# 5-Memories.net
KiCad netlist of a schematic drawn in Altium Designer
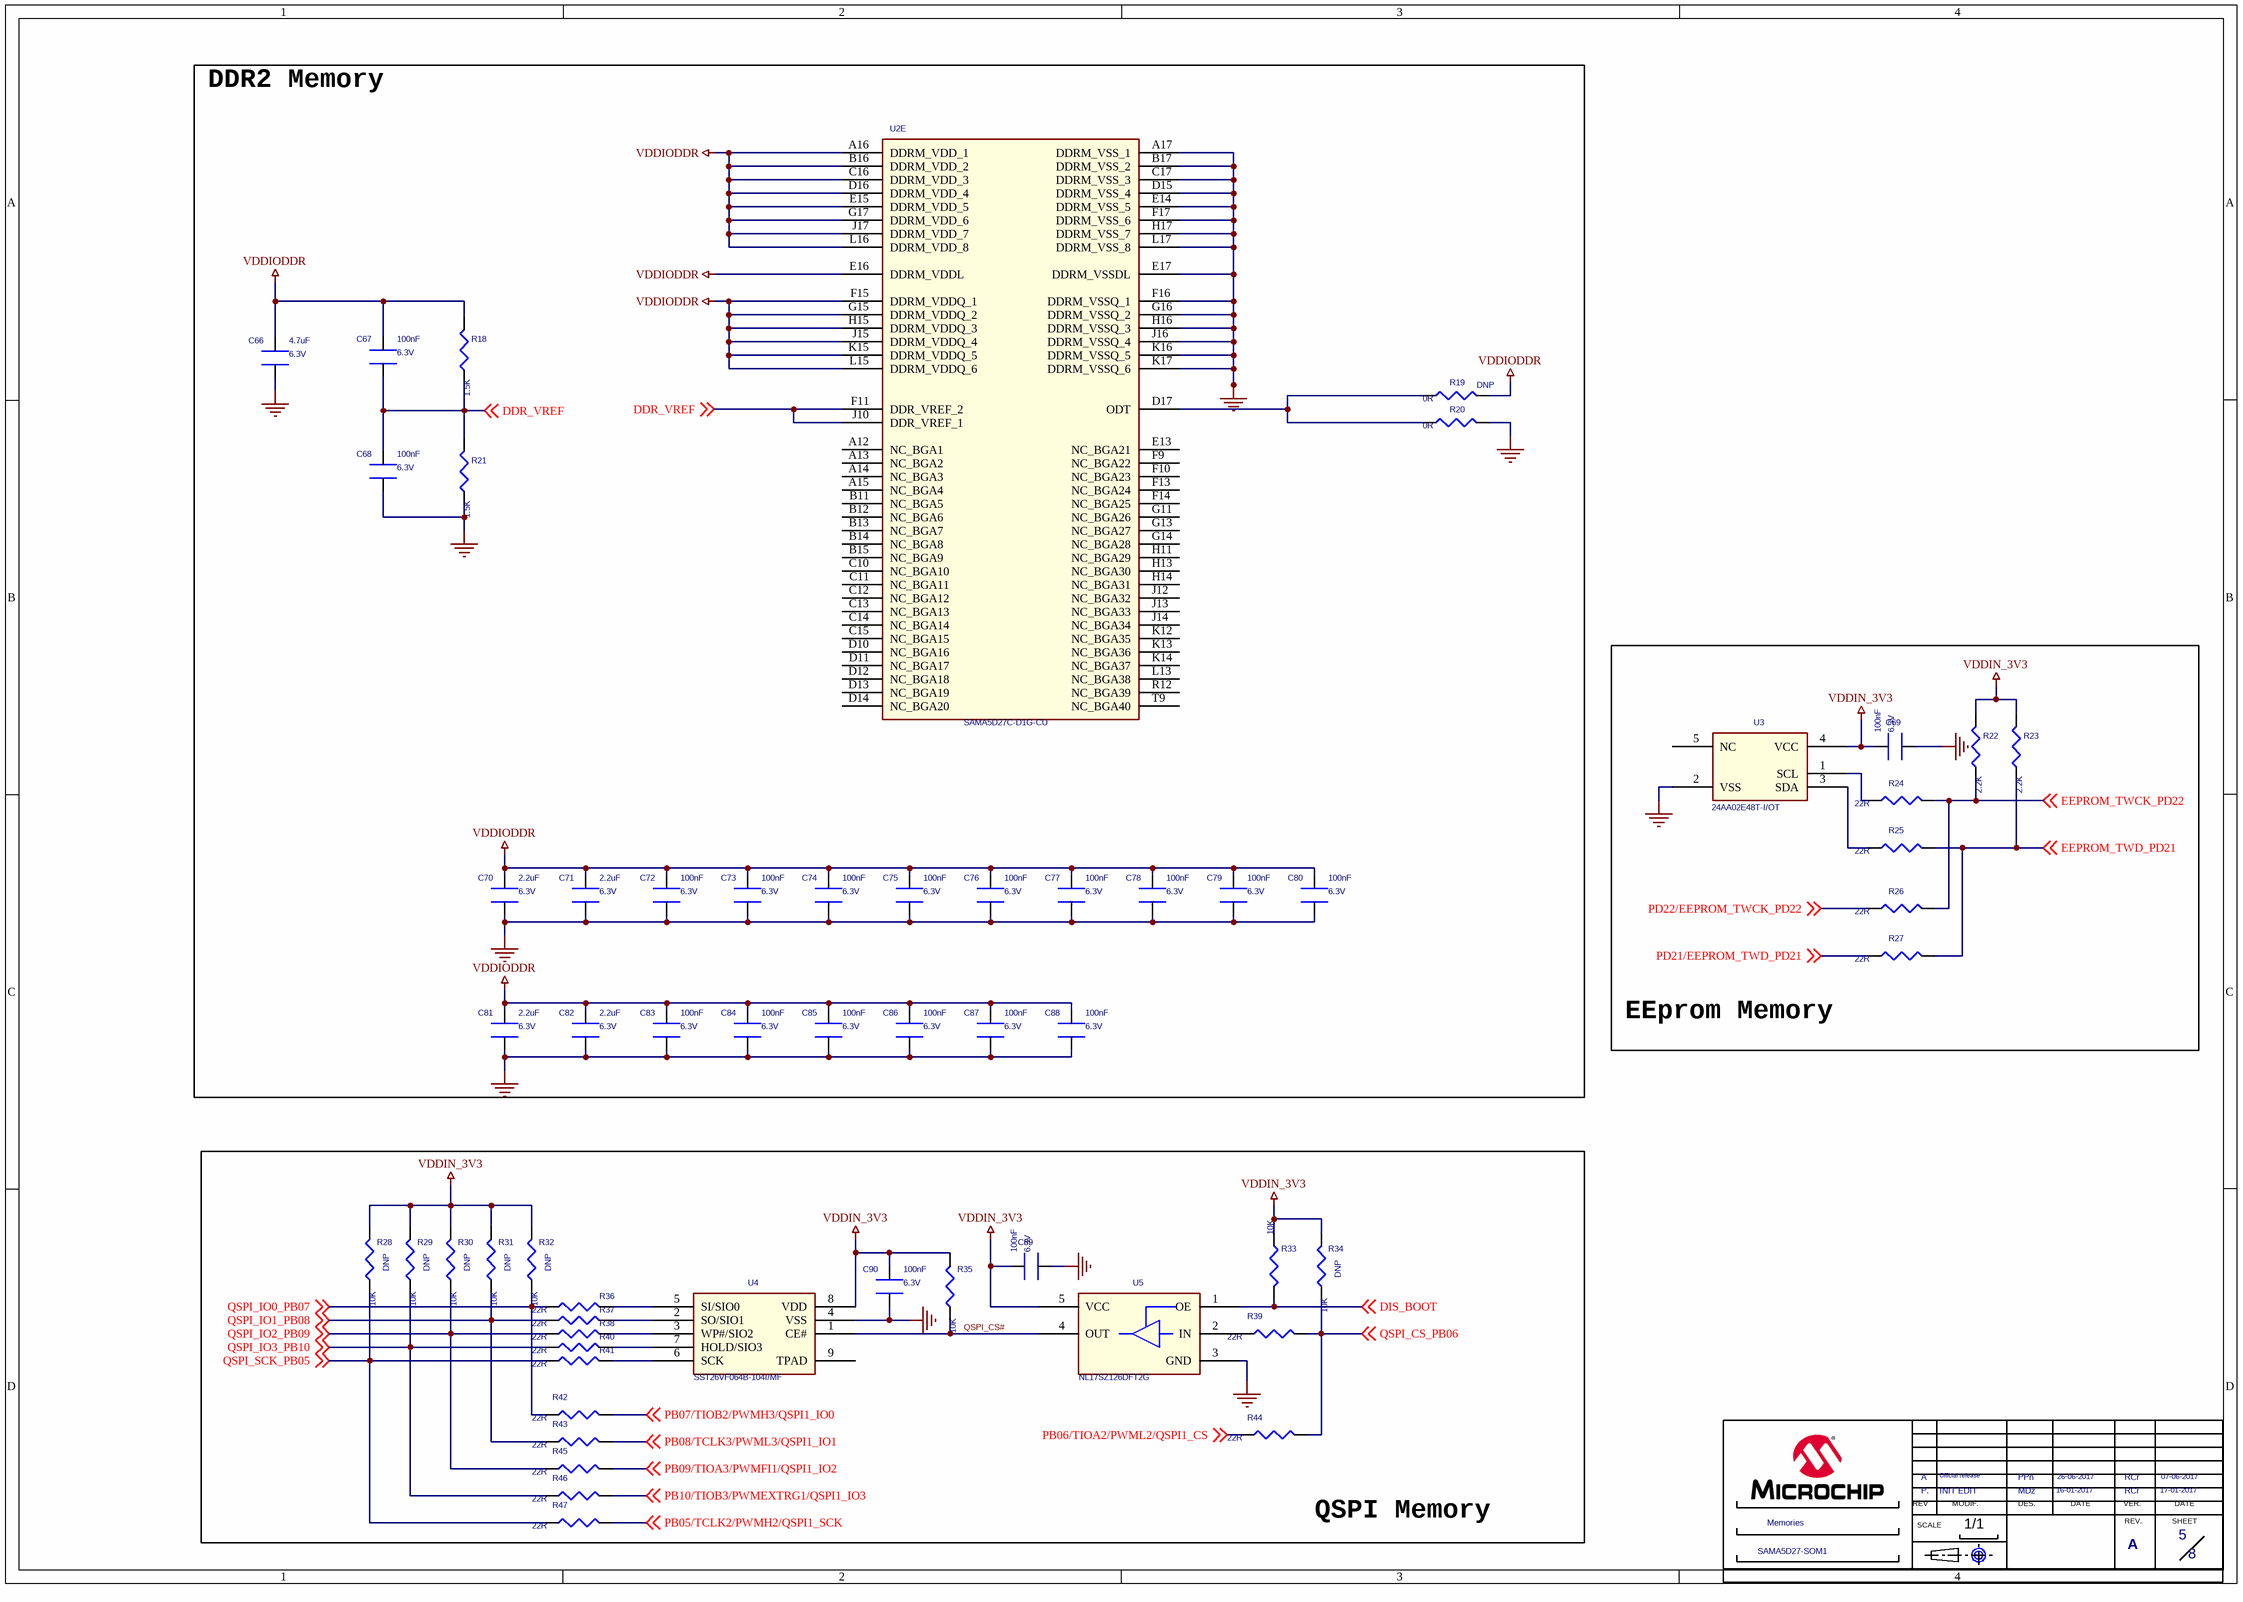
[diagram p0: 5-Memories.SchDoc]

(export (version "E")
  (design (tool "Eeschema 10.0.6"))
  (components
    (comp (ref "C66")
      (value "xpF x% xV")
      (footprint "C0402")
      (fields (field (name "TENSION") "6.3V") (field (name "VALEUR") "4.7uF") (field (name "HAUTEUR") "xmm"))
      (libsource (lib "*") (part "C0402-4.7uF-X5R-6.3V-10%"))
    )
    (comp (ref "C67")
      (value "xpF x% xV")
      (footprint "C0201")
      (fields (field (name "VALEUR") "100nF") (field (name "TENSION") "6.3V") (field (name "HAUTEUR") "xmm"))
      (libsource (lib "*") (part "C0201-100nF-X5R-6.3V"))
    )
    (comp (ref "C68")
      (value "xpF x% xV")
      (footprint "C0201")
      (fields (field (name "VALEUR") "100nF") (field (name "TENSION") "6.3V") (field (name "HAUTEUR") "xmm"))
      (libsource (lib "*") (part "C0201-100nF-X5R-6.3V"))
    )
    (comp (ref "C69")
      (value "xpF x% xV")
      (footprint "C0201")
      (fields (field (name "VALEUR") "100nF") (field (name "TENSION") "6.3V") (field (name "HAUTEUR") "xmm"))
      (libsource (lib "*") (part "C0201-100nF-X5R-6.3V"))
    )
    (comp (ref "C70")
      (value "xpF x% xV")
      (footprint "C0402")
      (fields (field (name "VALEUR") "2.2uF") (field (name "TENSION") "6.3V") (field (name "HAUTEUR") "xmm"))
      (libsource (lib "*") (part "C0402-2.2uF-X5R-6.3V"))
    )
    (comp (ref "C71")
      (value "xpF x% xV")
      (footprint "C0402")
      (fields (field (name "VALEUR") "2.2uF") (field (name "TENSION") "6.3V") (field (name "HAUTEUR") "xmm"))
      (libsource (lib "*") (part "C0402-2.2uF-X5R-6.3V"))
    )
    (comp (ref "C72")
      (value "xpF x% xV")
      (footprint "C0201")
      (fields (field (name "VALEUR") "100nF") (field (name "TENSION") "6.3V") (field (name "HAUTEUR") "xmm"))
      (libsource (lib "*") (part "C0201-100nF-X5R-6.3V"))
    )
    (comp (ref "C73")
      (value "xpF x% xV")
      (footprint "C0201")
      (fields (field (name "VALEUR") "100nF") (field (name "TENSION") "6.3V") (field (name "HAUTEUR") "xmm"))
      (libsource (lib "*") (part "C0201-100nF-X5R-6.3V"))
    )
    (comp (ref "C74")
      (value "xpF x% xV")
      (footprint "C0201")
      (fields (field (name "VALEUR") "100nF") (field (name "TENSION") "6.3V") (field (name "HAUTEUR") "xmm"))
      (libsource (lib "*") (part "C0201-100nF-X5R-6.3V"))
    )
    (comp (ref "C75")
      (value "xpF x% xV")
      (footprint "C0201")
      (fields (field (name "VALEUR") "100nF") (field (name "TENSION") "6.3V") (field (name "HAUTEUR") "xmm"))
      (libsource (lib "*") (part "C0201-100nF-X5R-6.3V"))
    )
    (comp (ref "C76")
      (value "xpF x% xV")
      (footprint "C0201")
      (fields (field (name "VALEUR") "100nF") (field (name "TENSION") "6.3V") (field (name "HAUTEUR") "xmm"))
      (libsource (lib "*") (part "C0201-100nF-X5R-6.3V"))
    )
    (comp (ref "C77")
      (value "xpF x% xV")
      (footprint "C0201")
      (fields (field (name "VALEUR") "100nF") (field (name "TENSION") "6.3V") (field (name "HAUTEUR") "xmm"))
      (libsource (lib "*") (part "C0201-100nF-X5R-6.3V"))
    )
    (comp (ref "C78")
      (value "xpF x% xV")
      (footprint "C0201")
      (fields (field (name "VALEUR") "100nF") (field (name "TENSION") "6.3V") (field (name "HAUTEUR") "xmm"))
      (libsource (lib "*") (part "C0201-100nF-X5R-6.3V"))
    )
    (comp (ref "C79")
      (value "xpF x% xV")
      (footprint "C0201")
      (fields (field (name "VALEUR") "100nF") (field (name "TENSION") "6.3V") (field (name "HAUTEUR") "xmm"))
      (libsource (lib "*") (part "C0201-100nF-X5R-6.3V"))
    )
    (comp (ref "C80")
      (value "xpF x% xV")
      (footprint "C0201")
      (fields (field (name "VALEUR") "100nF") (field (name "TENSION") "6.3V") (field (name "HAUTEUR") "xmm"))
      (libsource (lib "*") (part "C0201-100nF-X5R-6.3V"))
    )
    (comp (ref "C81")
      (value "xpF x% xV")
      (footprint "C0402")
      (fields (field (name "VALEUR") "2.2uF") (field (name "TENSION") "6.3V") (field (name "HAUTEUR") "xmm"))
      (libsource (lib "*") (part "C0402-2.2uF-X5R-6.3V"))
    )
    (comp (ref "C82")
      (value "xpF x% xV")
      (footprint "C0402")
      (fields (field (name "VALEUR") "2.2uF") (field (name "TENSION") "6.3V") (field (name "HAUTEUR") "xmm"))
      (libsource (lib "*") (part "C0402-2.2uF-X5R-6.3V"))
    )
    (comp (ref "C83")
      (value "xpF x% xV")
      (footprint "C0201")
      (fields (field (name "VALEUR") "100nF") (field (name "TENSION") "6.3V") (field (name "HAUTEUR") "xmm"))
      (libsource (lib "*") (part "C0201-100nF-X5R-6.3V"))
    )
    (comp (ref "C84")
      (value "xpF x% xV")
      (footprint "C0201")
      (fields (field (name "VALEUR") "100nF") (field (name "TENSION") "6.3V") (field (name "HAUTEUR") "xmm"))
      (libsource (lib "*") (part "C0201-100nF-X5R-6.3V"))
    )
    (comp (ref "C85")
      (value "xpF x% xV")
      (footprint "C0201")
      (fields (field (name "VALEUR") "100nF") (field (name "TENSION") "6.3V") (field (name "HAUTEUR") "xmm"))
      (libsource (lib "*") (part "C0201-100nF-X5R-6.3V"))
    )
    (comp (ref "C86")
      (value "xpF x% xV")
      (footprint "C0201")
      (fields (field (name "VALEUR") "100nF") (field (name "TENSION") "6.3V") (field (name "HAUTEUR") "xmm"))
      (libsource (lib "*") (part "C0201-100nF-X5R-6.3V"))
    )
    (comp (ref "C87")
      (value "xpF x% xV")
      (footprint "C0201")
      (fields (field (name "VALEUR") "100nF") (field (name "TENSION") "6.3V") (field (name "HAUTEUR") "xmm"))
      (libsource (lib "*") (part "C0201-100nF-X5R-6.3V"))
    )
    (comp (ref "C88")
      (value "xpF x% xV")
      (footprint "C0201")
      (fields (field (name "VALEUR") "100nF") (field (name "TENSION") "6.3V") (field (name "HAUTEUR") "xmm"))
      (libsource (lib "*") (part "C0201-100nF-X5R-6.3V"))
    )
    (comp (ref "C89")
      (value "xpF x% xV")
      (footprint "C0201")
      (fields (field (name "VALEUR") "100nF") (field (name "TENSION") "6.3V") (field (name "HAUTEUR") "xmm"))
      (libsource (lib "*") (part "C0201-100nF-X5R-6.3V"))
    )
    (comp (ref "C90")
      (value "xpF x% xV")
      (footprint "C0201")
      (fields (field (name "VALEUR") "100nF") (field (name "TENSION") "6.3V") (field (name "HAUTEUR") "xmm"))
      (libsource (lib "*") (part "C0201-100nF-X5R-6.3V"))
    )
    (comp (ref "R18")
      (value "xR x% xW")
      (footprint "R0201")
      (fields (field (name "VALEUR") "1.5K") (field (name "TOLERANCE") "1%"))
      (libsource (lib "*") (part "R0201-1.5K-1%"))
    )
    (comp (ref "R19")
      (value "xR x% xW")
      (footprint "R0201")
      (fields (field (name "VALEUR") "0R") (field (name "TOLERANCE") "x%") (field (name "DNP") "DNP"))
      (libsource (lib "*") (part "R0201-0R"))
    )
    (comp (ref "R20")
      (value "xR x% xW")
      (footprint "R0201")
      (fields (field (name "VALEUR") "0R") (field (name "TOLERANCE") "x%"))
      (libsource (lib "*") (part "R0201-0R"))
    )
    (comp (ref "R21")
      (value "xR x% xW")
      (footprint "R0201")
      (fields (field (name "VALEUR") "1.5K") (field (name "TOLERANCE") "1%"))
      (libsource (lib "*") (part "R0201-1.5K-1%"))
    )
    (comp (ref "R22")
      (value "xR x% xW")
      (footprint "R0201")
      (fields (field (name "TOLERANCE") "5%") (field (name "VALEUR") "2.2K"))
      (libsource (lib "*") (part "R0201-2.2K-5%"))
    )
    (comp (ref "R23")
      (value "xR x% xW")
      (footprint "R0201")
      (fields (field (name "TOLERANCE") "5%") (field (name "VALEUR") "2.2K"))
      (libsource (lib "*") (part "R0201-2.2K-5%"))
    )
    (comp (ref "R24")
      (value "xR x% xW")
      (footprint "R0201")
      (fields (field (name "VALEUR") "22R") (field (name "TOLERANCE") "5%"))
      (libsource (lib "*") (part "R0201-22R-5%"))
    )
    (comp (ref "R25")
      (value "xR x% xW")
      (footprint "R0201")
      (fields (field (name "VALEUR") "22R") (field (name "TOLERANCE") "5%"))
      (libsource (lib "*") (part "R0201-22R-5%"))
    )
    (comp (ref "R26")
      (value "xR x% xW")
      (footprint "R0201")
      (fields (field (name "VALEUR") "22R") (field (name "TOLERANCE") "5%"))
      (libsource (lib "*") (part "R0201-22R-5%"))
    )
    (comp (ref "R27")
      (value "xR x% xW")
      (footprint "R0201")
      (fields (field (name "VALEUR") "22R") (field (name "TOLERANCE") "5%"))
      (libsource (lib "*") (part "R0201-22R-5%"))
    )
    (comp (ref "R28")
      (value "xR x% xW")
      (footprint "R0201")
      (fields (field (name "TOLERANCE") "5%") (field (name "VALEUR") "10K") (field (name "DNP") "DNP"))
      (libsource (lib "*") (part "R0201-10K-5%-DNP"))
    )
    (comp (ref "R29")
      (value "xR x% xW")
      (footprint "R0201")
      (fields (field (name "TOLERANCE") "5%") (field (name "VALEUR") "10K") (field (name "DNP") "DNP"))
      (libsource (lib "*") (part "R0201-10K-5%-DNP"))
    )
    (comp (ref "R30")
      (value "xR x% xW")
      (footprint "R0201")
      (fields (field (name "TOLERANCE") "5%") (field (name "VALEUR") "10K") (field (name "DNP") "DNP"))
      (libsource (lib "*") (part "R0201-10K-5%-DNP"))
    )
    (comp (ref "R31")
      (value "xR x% xW")
      (footprint "R0201")
      (fields (field (name "TOLERANCE") "5%") (field (name "VALEUR") "10K") (field (name "DNP") "DNP"))
      (libsource (lib "*") (part "R0201-10K-5%-DNP"))
    )
    (comp (ref "R32")
      (value "xR x% xW")
      (footprint "R0201")
      (fields (field (name "TOLERANCE") "5%") (field (name "VALEUR") "10K") (field (name "DNP") "DNP"))
      (libsource (lib "*") (part "R0201-10K-5%-DNP"))
    )
    (comp (ref "R33")
      (value "xR x% xW")
      (footprint "R0201")
      (fields (field (name "VALEUR") "10K") (field (name "TOLERANCE") "5%"))
      (libsource (lib "*") (part "R0201-10K-5%"))
    )
    (comp (ref "R34")
      (value "xR x% xW")
      (footprint "R0201")
      (fields (field (name "TOLERANCE") "5%") (field (name "VALEUR") "10K") (field (name "DNP") "DNP"))
      (libsource (lib "*") (part "R0201-10K-5%-DNP"))
    )
    (comp (ref "R35")
      (value "xR x% xW")
      (footprint "R0201")
      (fields (field (name "VALEUR") "10K") (field (name "TOLERANCE") "5%"))
      (libsource (lib "*") (part "R0201-10K-5%"))
    )
    (comp (ref "R36")
      (value "xR x% xW")
      (footprint "R0201")
      (fields (field (name "VALEUR") "22R") (field (name "TOLERANCE") "5%"))
      (libsource (lib "*") (part "R0201-22R-5%"))
    )
    (comp (ref "R37")
      (value "xR x% xW")
      (footprint "R0201")
      (fields (field (name "VALEUR") "22R") (field (name "TOLERANCE") "5%"))
      (libsource (lib "*") (part "R0201-22R-5%"))
    )
    (comp (ref "R38")
      (value "xR x% xW")
      (footprint "R0201")
      (fields (field (name "VALEUR") "22R") (field (name "TOLERANCE") "5%"))
      (libsource (lib "*") (part "R0201-22R-5%"))
    )
    (comp (ref "R39")
      (value "xR x% xW")
      (footprint "R0201")
      (fields (field (name "VALEUR") "22R") (field (name "TOLERANCE") "5%"))
      (libsource (lib "*") (part "R0201-22R-5%"))
    )
    (comp (ref "R40")
      (value "xR x% xW")
      (footprint "R0201")
      (fields (field (name "VALEUR") "22R") (field (name "TOLERANCE") "5%"))
      (libsource (lib "*") (part "R0201-22R-5%"))
    )
    (comp (ref "R41")
      (value "xR x% xW")
      (footprint "R0201")
      (fields (field (name "VALEUR") "22R") (field (name "TOLERANCE") "5%"))
      (libsource (lib "*") (part "R0201-22R-5%"))
    )
    (comp (ref "R42")
      (value "xR x% xW")
      (footprint "R0201")
      (fields (field (name "VALEUR") "22R") (field (name "TOLERANCE") "5%"))
      (libsource (lib "*") (part "R0201-22R-5%"))
    )
    (comp (ref "R43")
      (value "xR x% xW")
      (footprint "R0201")
      (fields (field (name "VALEUR") "22R") (field (name "TOLERANCE") "5%"))
      (libsource (lib "*") (part "R0201-22R-5%"))
    )
    (comp (ref "R44")
      (value "xR x% xW")
      (footprint "R0201")
      (fields (field (name "VALEUR") "22R") (field (name "TOLERANCE") "5%"))
      (libsource (lib "*") (part "R0201-22R-5%"))
    )
    (comp (ref "R45")
      (value "xR x% xW")
      (footprint "R0201")
      (fields (field (name "VALEUR") "22R") (field (name "TOLERANCE") "5%"))
      (libsource (lib "*") (part "R0201-22R-5%"))
    )
    (comp (ref "R46")
      (value "xR x% xW")
      (footprint "R0201")
      (fields (field (name "VALEUR") "22R") (field (name "TOLERANCE") "5%"))
      (libsource (lib "*") (part "R0201-22R-5%"))
    )
    (comp (ref "R47")
      (value "xR x% xW")
      (footprint "R0201")
      (fields (field (name "VALEUR") "22R") (field (name "TOLERANCE") "5%"))
      (libsource (lib "*") (part "R0201-22R-5%"))
    )
    (comp (ref "U2")
      (value "SAMA5D27C-D1G-CU")
      (footprint "BGA289_02")
      (libsource (lib "*") (part "SAMA5D27C-D1G-CU"))
    )
    (comp (ref "U3")
      (value "24AA02E48T-I/OT")
      (footprint "SOT23-5_02")
      (libsource (lib "*") (part "24AA02E48T-I-OT"))
    )
    (comp (ref "U4")
      (value "SST26VF064B-104I/MF")
      (footprint "WDFN08_01")
      (libsource (lib "*") (part "SST26VF064B-104I-MF"))
    )
    (comp (ref "U5")
      (value "NL17SZ126DFT2G")
      (footprint "SOT353_01")
      (libsource (lib "*") (part "NL17SZ126DFT2G"))
    )
  )
  (nets
    (net (code "1") (name "/QSPI_CS#") (class "Default")
      (node (ref "R35") (pin "1") (pinfunction "1_1") (pintype "passive"))
      (node (ref "U4") (pin "1") (pinfunction "CE#_1") (pintype "passive"))
      (node (ref "U5") (pin "4") (pinfunction "OUT_4") (pintype "passive"))
    )
    (net (code "2") (name "DDR_VREF") (class "Default")
      (node (ref "C67") (pin "1") (pinfunction "1_1") (pintype "passive"))
      (node (ref "C68") (pin "2") (pinfunction "2_2") (pintype "passive"))
      (node (ref "R18") (pin "1") (pinfunction "1_1") (pintype "passive"))
      (node (ref "R21") (pin "2") (pinfunction "2_2") (pintype "passive"))
      (node (ref "U2") (pin "F11") (pinfunction "DDR_VREF_2_F11") (pintype "passive"))
      (node (ref "U2") (pin "J10") (pinfunction "DDR_VREF_1_J10") (pintype "passive"))
    )
    (net (code "3") (name "DIS_BOOT") (class "Default")
      (node (ref "R33") (pin "2") (pinfunction "2_2") (pintype "passive"))
      (node (ref "U5") (pin "1") (pinfunction "OE_1") (pintype "passive"))
    )
    (net (code "4") (name "EEPROM_TWCK_PD22") (class "Default")
      (node (ref "R22") (pin "1") (pinfunction "1_1") (pintype "passive"))
      (node (ref "R24") (pin "2") (pinfunction "2_2") (pintype "passive"))
      (node (ref "R26") (pin "2") (pinfunction "2_2") (pintype "passive"))
    )
    (net (code "5") (name "EEPROM_TWD_PD21") (class "Default")
      (node (ref "R23") (pin "1") (pinfunction "1_1") (pintype "passive"))
      (node (ref "R25") (pin "2") (pinfunction "2_2") (pintype "passive"))
      (node (ref "R27") (pin "2") (pinfunction "2_2") (pintype "passive"))
    )
    (net (code "6") (name "GND") (class "Default")
      (node (ref "C66") (pin "1") (pinfunction "1_1") (pintype "passive"))
      (node (ref "C68") (pin "1") (pinfunction "1_1") (pintype "passive"))
      (node (ref "C69") (pin "1") (pinfunction "1_1") (pintype "passive"))
      (node (ref "C70") (pin "1") (pinfunction "1_1") (pintype "passive"))
      (node (ref "C71") (pin "1") (pinfunction "1_1") (pintype "passive"))
      (node (ref "C72") (pin "1") (pinfunction "1_1") (pintype "passive"))
      (node (ref "C73") (pin "1") (pinfunction "1_1") (pintype "passive"))
      (node (ref "C74") (pin "1") (pinfunction "1_1") (pintype "passive"))
      (node (ref "C75") (pin "1") (pinfunction "1_1") (pintype "passive"))
      (node (ref "C76") (pin "1") (pinfunction "1_1") (pintype "passive"))
      (node (ref "C77") (pin "1") (pinfunction "1_1") (pintype "passive"))
      (node (ref "C78") (pin "1") (pinfunction "1_1") (pintype "passive"))
      (node (ref "C79") (pin "1") (pinfunction "1_1") (pintype "passive"))
      (node (ref "C80") (pin "1") (pinfunction "1_1") (pintype "passive"))
      (node (ref "C81") (pin "1") (pinfunction "1_1") (pintype "passive"))
      (node (ref "C82") (pin "1") (pinfunction "1_1") (pintype "passive"))
      (node (ref "C83") (pin "1") (pinfunction "1_1") (pintype "passive"))
      (node (ref "C84") (pin "1") (pinfunction "1_1") (pintype "passive"))
      (node (ref "C85") (pin "1") (pinfunction "1_1") (pintype "passive"))
      (node (ref "C86") (pin "1") (pinfunction "1_1") (pintype "passive"))
      (node (ref "C87") (pin "1") (pinfunction "1_1") (pintype "passive"))
      (node (ref "C88") (pin "1") (pinfunction "1_1") (pintype "passive"))
      (node (ref "C89") (pin "1") (pinfunction "1_1") (pintype "passive"))
      (node (ref "C90") (pin "1") (pinfunction "1_1") (pintype "passive"))
      (node (ref "R20") (pin "2") (pinfunction "2_2") (pintype "passive"))
      (node (ref "R21") (pin "1") (pinfunction "1_1") (pintype "passive"))
      (node (ref "U2") (pin "A17") (pinfunction "DDRM_VSS_1_A17") (pintype "passive"))
      (node (ref "U2") (pin "B17") (pinfunction "DDRM_VSS_2_B17") (pintype "passive"))
      (node (ref "U2") (pin "C17") (pinfunction "DDRM_VSS_3_C17") (pintype "passive"))
      (node (ref "U2") (pin "D15") (pinfunction "DDRM_VSS_4_D15") (pintype "passive"))
      (node (ref "U2") (pin "E14") (pinfunction "DDRM_VSS_5_E14") (pintype "passive"))
      (node (ref "U2") (pin "E17") (pinfunction "DDRM_VSSDL_E17") (pintype "passive"))
      (node (ref "U2") (pin "F16") (pinfunction "DDRM_VSSQ_1_F16") (pintype "passive"))
      (node (ref "U2") (pin "F17") (pinfunction "DDRM_VSS_6_F17") (pintype "passive"))
      (node (ref "U2") (pin "G16") (pinfunction "DDRM_VSSQ_2_G16") (pintype "passive"))
      (node (ref "U2") (pin "H16") (pinfunction "DDRM_VSSQ_3_H16") (pintype "passive"))
      (node (ref "U2") (pin "H17") (pinfunction "DDRM_VSS_7_H17") (pintype "passive"))
      (node (ref "U2") (pin "J16") (pinfunction "DDRM_VSSQ_4_J16") (pintype "passive"))
      (node (ref "U2") (pin "K16") (pinfunction "DDRM_VSSQ_5_K16") (pintype "passive"))
      (node (ref "U2") (pin "K17") (pinfunction "DDRM_VSSQ_6_K17") (pintype "passive"))
      (node (ref "U2") (pin "L17") (pinfunction "DDRM_VSS_8_L17") (pintype "passive"))
      (node (ref "U3") (pin "2") (pinfunction "VSS_2") (pintype "passive"))
      (node (ref "U4") (pin "4") (pinfunction "VSS_4") (pintype "passive"))
      (node (ref "U5") (pin "3") (pinfunction "GND_3") (pintype "passive"))
    )
    (net (code "7") (name "Net-(U2E-ODT)") (class "Default")
      (node (ref "R19") (pin "1") (pinfunction "1_1") (pintype "passive"))
      (node (ref "R20") (pin "1") (pinfunction "1_1") (pintype "passive"))
      (node (ref "U2") (pin "D17") (pinfunction "ODT_D17") (pintype "passive"))
    )
    (net (code "8") (name "Net-(U3-SCL)") (class "Default")
      (node (ref "R24") (pin "1") (pinfunction "1_1") (pintype "passive"))
      (node (ref "U3") (pin "1") (pinfunction "SCL_1") (pintype "passive"))
    )
    (net (code "9") (name "Net-(U3-SDA)") (class "Default")
      (node (ref "R25") (pin "1") (pinfunction "1_1") (pintype "passive"))
      (node (ref "U3") (pin "3") (pinfunction "SDA_3") (pintype "passive"))
    )
    (net (code "10") (name "Net-(U4-HOLD{slash}SIO3)") (class "Default")
      (node (ref "R40") (pin "2") (pinfunction "2_2") (pintype "passive"))
      (node (ref "U4") (pin "7") (pinfunction "HOLD/SIO3_7") (pintype "passive"))
    )
    (net (code "11") (name "Net-(U4-SCK)") (class "Default")
      (node (ref "R41") (pin "2") (pinfunction "2_2") (pintype "passive"))
      (node (ref "U4") (pin "6") (pinfunction "SCK_6") (pintype "passive"))
    )
    (net (code "12") (name "Net-(U4-SI{slash}SIO0)") (class "Default")
      (node (ref "R36") (pin "2") (pinfunction "2_2") (pintype "passive"))
      (node (ref "U4") (pin "5") (pinfunction "SI/SIO0_5") (pintype "passive"))
    )
    (net (code "13") (name "Net-(U4-SO{slash}SIO1)") (class "Default")
      (node (ref "R37") (pin "2") (pinfunction "2_2") (pintype "passive"))
      (node (ref "U4") (pin "2") (pinfunction "SO/SIO1_2") (pintype "passive"))
    )
    (net (code "14") (name "Net-(U4-WP#{slash}SIO2)") (class "Default")
      (node (ref "R38") (pin "2") (pinfunction "2_2") (pintype "passive"))
      (node (ref "U4") (pin "3") (pinfunction "WP#/SIO2_3") (pintype "passive"))
    )
    (net (code "15") (name "Net-(U5-IN)") (class "Default")
      (node (ref "R39") (pin "1") (pinfunction "1_1") (pintype "passive"))
      (node (ref "U5") (pin "2") (pinfunction "IN_2") (pintype "passive"))
    )
    (net (code "16") (name "PB05{slash}TCLK2{slash}PWMH2{slash}QSPI1_SCK") (class "Default")
      (node (ref "R47") (pin "2") (pinfunction "2_2") (pintype "passive"))
    )
    (net (code "17") (name "PB06{slash}TIOA2{slash}PWML2{slash}QSPI1_CS") (class "Default")
      (node (ref "R44") (pin "1") (pinfunction "1_1") (pintype "passive"))
    )
    (net (code "18") (name "PB07{slash}TIOB2{slash}PWMH3{slash}QSPI1_IO0") (class "Default")
      (node (ref "R42") (pin "2") (pinfunction "2_2") (pintype "passive"))
    )
    (net (code "19") (name "PB08{slash}TCLK3{slash}PWML3{slash}QSPI1_IO1") (class "Default")
      (node (ref "R43") (pin "2") (pinfunction "2_2") (pintype "passive"))
    )
    (net (code "20") (name "PB09{slash}TIOA3{slash}PWMFI1{slash}QSPI1_IO2") (class "Default")
      (node (ref "R45") (pin "2") (pinfunction "2_2") (pintype "passive"))
    )
    (net (code "21") (name "PB10{slash}TIOB3{slash}PWMEXTRG1{slash}QSPI1_IO3") (class "Default")
      (node (ref "R46") (pin "2") (pinfunction "2_2") (pintype "passive"))
    )
    (net (code "22") (name "PD21{slash}EEPROM_TWD_PD21") (class "Default")
      (node (ref "R27") (pin "1") (pinfunction "1_1") (pintype "passive"))
    )
    (net (code "23") (name "PD22{slash}EEPROM_TWCK_PD22") (class "Default")
      (node (ref "R26") (pin "1") (pinfunction "1_1") (pintype "passive"))
    )
    (net (code "24") (name "QSPI_CS_PB06") (class "Default")
      (node (ref "R34") (pin "1") (pinfunction "1_1") (pintype "passive"))
      (node (ref "R39") (pin "2") (pinfunction "2_2") (pintype "passive"))
      (node (ref "R44") (pin "2") (pinfunction "2_2") (pintype "passive"))
    )
    (net (code "25") (name "QSPI_IO0_PB07") (class "Default")
      (node (ref "R32") (pin "1") (pinfunction "1_1") (pintype "passive"))
      (node (ref "R36") (pin "1") (pinfunction "1_1") (pintype "passive"))
      (node (ref "R42") (pin "1") (pinfunction "1_1") (pintype "passive"))
    )
    (net (code "26") (name "QSPI_IO1_PB08") (class "Default")
      (node (ref "R31") (pin "1") (pinfunction "1_1") (pintype "passive"))
      (node (ref "R37") (pin "1") (pinfunction "1_1") (pintype "passive"))
      (node (ref "R43") (pin "1") (pinfunction "1_1") (pintype "passive"))
    )
    (net (code "27") (name "QSPI_IO2_PB09") (class "Default")
      (node (ref "R30") (pin "1") (pinfunction "1_1") (pintype "passive"))
      (node (ref "R38") (pin "1") (pinfunction "1_1") (pintype "passive"))
      (node (ref "R45") (pin "1") (pinfunction "1_1") (pintype "passive"))
    )
    (net (code "28") (name "QSPI_IO3_PB10") (class "Default")
      (node (ref "R29") (pin "1") (pinfunction "1_1") (pintype "passive"))
      (node (ref "R40") (pin "1") (pinfunction "1_1") (pintype "passive"))
      (node (ref "R46") (pin "1") (pinfunction "1_1") (pintype "passive"))
    )
    (net (code "29") (name "QSPI_SCK_PB05") (class "Default")
      (node (ref "R28") (pin "1") (pinfunction "1_1") (pintype "passive"))
      (node (ref "R41") (pin "1") (pinfunction "1_1") (pintype "passive"))
      (node (ref "R47") (pin "1") (pinfunction "1_1") (pintype "passive"))
    )
    (net (code "30") (name "VDDIN_3V3") (class "Default")
      (node (ref "C69") (pin "2") (pinfunction "2_2") (pintype "passive"))
      (node (ref "C89") (pin "2") (pinfunction "2_2") (pintype "passive"))
      (node (ref "C90") (pin "2") (pinfunction "2_2") (pintype "passive"))
      (node (ref "R22") (pin "2") (pinfunction "2_2") (pintype "passive"))
      (node (ref "R23") (pin "2") (pinfunction "2_2") (pintype "passive"))
      (node (ref "R28") (pin "2") (pinfunction "2_2") (pintype "passive"))
      (node (ref "R29") (pin "2") (pinfunction "2_2") (pintype "passive"))
      (node (ref "R30") (pin "2") (pinfunction "2_2") (pintype "passive"))
      (node (ref "R31") (pin "2") (pinfunction "2_2") (pintype "passive"))
      (node (ref "R32") (pin "2") (pinfunction "2_2") (pintype "passive"))
      (node (ref "R33") (pin "1") (pinfunction "1_1") (pintype "passive"))
      (node (ref "R34") (pin "2") (pinfunction "2_2") (pintype "passive"))
      (node (ref "R35") (pin "2") (pinfunction "2_2") (pintype "passive"))
      (node (ref "U3") (pin "4") (pinfunction "VCC_4") (pintype "passive"))
      (node (ref "U4") (pin "8") (pinfunction "VDD_8") (pintype "passive"))
      (node (ref "U5") (pin "5") (pinfunction "VCC_5") (pintype "passive"))
    )
    (net (code "31") (name "VDDIODDR") (class "Default")
      (node (ref "C66") (pin "2") (pinfunction "2_2") (pintype "passive"))
      (node (ref "C67") (pin "2") (pinfunction "2_2") (pintype "passive"))
      (node (ref "C70") (pin "2") (pinfunction "2_2") (pintype "passive"))
      (node (ref "C71") (pin "2") (pinfunction "2_2") (pintype "passive"))
      (node (ref "C72") (pin "2") (pinfunction "2_2") (pintype "passive"))
      (node (ref "C73") (pin "2") (pinfunction "2_2") (pintype "passive"))
      (node (ref "C74") (pin "2") (pinfunction "2_2") (pintype "passive"))
      (node (ref "C75") (pin "2") (pinfunction "2_2") (pintype "passive"))
      (node (ref "C76") (pin "2") (pinfunction "2_2") (pintype "passive"))
      (node (ref "C77") (pin "2") (pinfunction "2_2") (pintype "passive"))
      (node (ref "C78") (pin "2") (pinfunction "2_2") (pintype "passive"))
      (node (ref "C79") (pin "2") (pinfunction "2_2") (pintype "passive"))
      (node (ref "C80") (pin "2") (pinfunction "2_2") (pintype "passive"))
      (node (ref "C81") (pin "2") (pinfunction "2_2") (pintype "passive"))
      (node (ref "C82") (pin "2") (pinfunction "2_2") (pintype "passive"))
      (node (ref "C83") (pin "2") (pinfunction "2_2") (pintype "passive"))
      (node (ref "C84") (pin "2") (pinfunction "2_2") (pintype "passive"))
      (node (ref "C85") (pin "2") (pinfunction "2_2") (pintype "passive"))
      (node (ref "C86") (pin "2") (pinfunction "2_2") (pintype "passive"))
      (node (ref "C87") (pin "2") (pinfunction "2_2") (pintype "passive"))
      (node (ref "C88") (pin "2") (pinfunction "2_2") (pintype "passive"))
      (node (ref "R18") (pin "2") (pinfunction "2_2") (pintype "passive"))
      (node (ref "R19") (pin "2") (pinfunction "2_2") (pintype "passive"))
      (node (ref "U2") (pin "A16") (pinfunction "DDRM_VDD_1_A16") (pintype "passive"))
      (node (ref "U2") (pin "B16") (pinfunction "DDRM_VDD_2_B16") (pintype "passive"))
      (node (ref "U2") (pin "C16") (pinfunction "DDRM_VDD_3_C16") (pintype "passive"))
      (node (ref "U2") (pin "D16") (pinfunction "DDRM_VDD_4_D16") (pintype "passive"))
      (node (ref "U2") (pin "E15") (pinfunction "DDRM_VDD_5_E15") (pintype "passive"))
      (node (ref "U2") (pin "E16") (pinfunction "DDRM_VDDL_E16") (pintype "passive"))
      (node (ref "U2") (pin "F15") (pinfunction "DDRM_VDDQ_1_F15") (pintype "passive"))
      (node (ref "U2") (pin "G15") (pinfunction "DDRM_VDDQ_2_G15") (pintype "passive"))
      (node (ref "U2") (pin "G17") (pinfunction "DDRM_VDD_6_G17") (pintype "passive"))
      (node (ref "U2") (pin "H15") (pinfunction "DDRM_VDDQ_3_H15") (pintype "passive"))
      (node (ref "U2") (pin "J15") (pinfunction "DDRM_VDDQ_4_J15") (pintype "passive"))
      (node (ref "U2") (pin "J17") (pinfunction "DDRM_VDD_7_J17") (pintype "passive"))
      (node (ref "U2") (pin "K15") (pinfunction "DDRM_VDDQ_5_K15") (pintype "passive"))
      (node (ref "U2") (pin "L15") (pinfunction "DDRM_VDDQ_6_L15") (pintype "passive"))
      (node (ref "U2") (pin "L16") (pinfunction "DDRM_VDD_8_L16") (pintype "passive"))
    )
    (net (code "32") (name "unconnected-(U2E-NC_BGA1-PadA12)") (class "Default")
      (node (ref "U2") (pin "A12") (pinfunction "NC_BGA1_A12") (pintype "passive"))
    )
    (net (code "33") (name "unconnected-(U2E-NC_BGA2-PadA13)") (class "Default")
      (node (ref "U2") (pin "A13") (pinfunction "NC_BGA2_A13") (pintype "passive"))
    )
    (net (code "34") (name "unconnected-(U2E-NC_BGA3-PadA14)") (class "Default")
      (node (ref "U2") (pin "A14") (pinfunction "NC_BGA3_A14") (pintype "passive"))
    )
    (net (code "35") (name "unconnected-(U2E-NC_BGA4-PadA15)") (class "Default")
      (node (ref "U2") (pin "A15") (pinfunction "NC_BGA4_A15") (pintype "passive"))
    )
    (net (code "36") (name "unconnected-(U2E-NC_BGA5-PadB11)") (class "Default")
      (node (ref "U2") (pin "B11") (pinfunction "NC_BGA5_B11") (pintype "passive"))
    )
    (net (code "37") (name "unconnected-(U2E-NC_BGA6-PadB12)") (class "Default")
      (node (ref "U2") (pin "B12") (pinfunction "NC_BGA6_B12") (pintype "passive"))
    )
    (net (code "38") (name "unconnected-(U2E-NC_BGA7-PadB13)") (class "Default")
      (node (ref "U2") (pin "B13") (pinfunction "NC_BGA7_B13") (pintype "passive"))
    )
    (net (code "39") (name "unconnected-(U2E-NC_BGA8-PadB14)") (class "Default")
      (node (ref "U2") (pin "B14") (pinfunction "NC_BGA8_B14") (pintype "passive"))
    )
    (net (code "40") (name "unconnected-(U2E-NC_BGA9-PadB15)") (class "Default")
      (node (ref "U2") (pin "B15") (pinfunction "NC_BGA9_B15") (pintype "passive"))
    )
    (net (code "41") (name "unconnected-(U2E-NC_BGA10-PadC10)") (class "Default")
      (node (ref "U2") (pin "C10") (pinfunction "NC_BGA10_C10") (pintype "passive"))
    )
    (net (code "42") (name "unconnected-(U2E-NC_BGA11-PadC11)") (class "Default")
      (node (ref "U2") (pin "C11") (pinfunction "NC_BGA11_C11") (pintype "passive"))
    )
    (net (code "43") (name "unconnected-(U2E-NC_BGA12-PadC12)") (class "Default")
      (node (ref "U2") (pin "C12") (pinfunction "NC_BGA12_C12") (pintype "passive"))
    )
    (net (code "44") (name "unconnected-(U2E-NC_BGA13-PadC13)") (class "Default")
      (node (ref "U2") (pin "C13") (pinfunction "NC_BGA13_C13") (pintype "passive"))
    )
    (net (code "45") (name "unconnected-(U2E-NC_BGA14-PadC14)") (class "Default")
      (node (ref "U2") (pin "C14") (pinfunction "NC_BGA14_C14") (pintype "passive"))
    )
    (net (code "46") (name "unconnected-(U2E-NC_BGA15-PadC15)") (class "Default")
      (node (ref "U2") (pin "C15") (pinfunction "NC_BGA15_C15") (pintype "passive"))
    )
    (net (code "47") (name "unconnected-(U2E-NC_BGA16-PadD10)") (class "Default")
      (node (ref "U2") (pin "D10") (pinfunction "NC_BGA16_D10") (pintype "passive"))
    )
    (net (code "48") (name "unconnected-(U2E-NC_BGA17-PadD11)") (class "Default")
      (node (ref "U2") (pin "D11") (pinfunction "NC_BGA17_D11") (pintype "passive"))
    )
    (net (code "49") (name "unconnected-(U2E-NC_BGA18-PadD12)") (class "Default")
      (node (ref "U2") (pin "D12") (pinfunction "NC_BGA18_D12") (pintype "passive"))
    )
    (net (code "50") (name "unconnected-(U2E-NC_BGA19-PadD13)") (class "Default")
      (node (ref "U2") (pin "D13") (pinfunction "NC_BGA19_D13") (pintype "passive"))
    )
    (net (code "51") (name "unconnected-(U2E-NC_BGA20-PadD14)") (class "Default")
      (node (ref "U2") (pin "D14") (pinfunction "NC_BGA20_D14") (pintype "passive"))
    )
    (net (code "52") (name "unconnected-(U2E-NC_BGA21-PadE13)") (class "Default")
      (node (ref "U2") (pin "E13") (pinfunction "NC_BGA21_E13") (pintype "passive"))
    )
    (net (code "53") (name "unconnected-(U2E-NC_BGA22-PadF9)") (class "Default")
      (node (ref "U2") (pin "F9") (pinfunction "NC_BGA22_F9") (pintype "passive"))
    )
    (net (code "54") (name "unconnected-(U2E-NC_BGA23-PadF10)") (class "Default")
      (node (ref "U2") (pin "F10") (pinfunction "NC_BGA23_F10") (pintype "passive"))
    )
    (net (code "55") (name "unconnected-(U2E-NC_BGA24-PadF13)") (class "Default")
      (node (ref "U2") (pin "F13") (pinfunction "NC_BGA24_F13") (pintype "passive"))
    )
    (net (code "56") (name "unconnected-(U2E-NC_BGA25-PadF14)") (class "Default")
      (node (ref "U2") (pin "F14") (pinfunction "NC_BGA25_F14") (pintype "passive"))
    )
    (net (code "57") (name "unconnected-(U2E-NC_BGA26-PadG11)") (class "Default")
      (node (ref "U2") (pin "G11") (pinfunction "NC_BGA26_G11") (pintype "passive"))
    )
    (net (code "58") (name "unconnected-(U2E-NC_BGA27-PadG13)") (class "Default")
      (node (ref "U2") (pin "G13") (pinfunction "NC_BGA27_G13") (pintype "passive"))
    )
    (net (code "59") (name "unconnected-(U2E-NC_BGA28-PadG14)") (class "Default")
      (node (ref "U2") (pin "G14") (pinfunction "NC_BGA28_G14") (pintype "passive"))
    )
    (net (code "60") (name "unconnected-(U2E-NC_BGA29-PadH11)") (class "Default")
      (node (ref "U2") (pin "H11") (pinfunction "NC_BGA29_H11") (pintype "passive"))
    )
    (net (code "61") (name "unconnected-(U2E-NC_BGA30-PadH13)") (class "Default")
      (node (ref "U2") (pin "H13") (pinfunction "NC_BGA30_H13") (pintype "passive"))
    )
    (net (code "62") (name "unconnected-(U2E-NC_BGA31-PadH14)") (class "Default")
      (node (ref "U2") (pin "H14") (pinfunction "NC_BGA31_H14") (pintype "passive"))
    )
    (net (code "63") (name "unconnected-(U2E-NC_BGA32-PadJ12)") (class "Default")
      (node (ref "U2") (pin "J12") (pinfunction "NC_BGA32_J12") (pintype "passive"))
    )
    (net (code "64") (name "unconnected-(U2E-NC_BGA33-PadJ13)") (class "Default")
      (node (ref "U2") (pin "J13") (pinfunction "NC_BGA33_J13") (pintype "passive"))
    )
    (net (code "65") (name "unconnected-(U2E-NC_BGA34-PadJ14)") (class "Default")
      (node (ref "U2") (pin "J14") (pinfunction "NC_BGA34_J14") (pintype "passive"))
    )
    (net (code "66") (name "unconnected-(U2E-NC_BGA35-PadK12)") (class "Default")
      (node (ref "U2") (pin "K12") (pinfunction "NC_BGA35_K12") (pintype "passive"))
    )
    (net (code "67") (name "unconnected-(U2E-NC_BGA36-PadK13)") (class "Default")
      (node (ref "U2") (pin "K13") (pinfunction "NC_BGA36_K13") (pintype "passive"))
    )
    (net (code "68") (name "unconnected-(U2E-NC_BGA37-PadK14)") (class "Default")
      (node (ref "U2") (pin "K14") (pinfunction "NC_BGA37_K14") (pintype "passive"))
    )
    (net (code "69") (name "unconnected-(U2E-NC_BGA38-PadL13)") (class "Default")
      (node (ref "U2") (pin "L13") (pinfunction "NC_BGA38_L13") (pintype "passive"))
    )
    (net (code "70") (name "unconnected-(U2E-NC_BGA39-PadR12)") (class "Default")
      (node (ref "U2") (pin "R12") (pinfunction "NC_BGA39_R12") (pintype "passive"))
    )
    (net (code "71") (name "unconnected-(U2E-NC_BGA40-PadT9)") (class "Default")
      (node (ref "U2") (pin "T9") (pinfunction "NC_BGA40_T9") (pintype "passive"))
    )
    (net (code "72") (name "unconnected-(U3-NC-Pad5)") (class "Default")
      (node (ref "U3") (pin "5") (pinfunction "NC_5") (pintype "passive"))
    )
    (net (code "73") (name "unconnected-(U4-TPAD-Pad9)") (class "Default")
      (node (ref "U4") (pin "9") (pinfunction "TPAD_9") (pintype "passive"))
    )
  )
)
